# Battery4p.net
KiCad netlist of a schematic drawn in Altium Designer
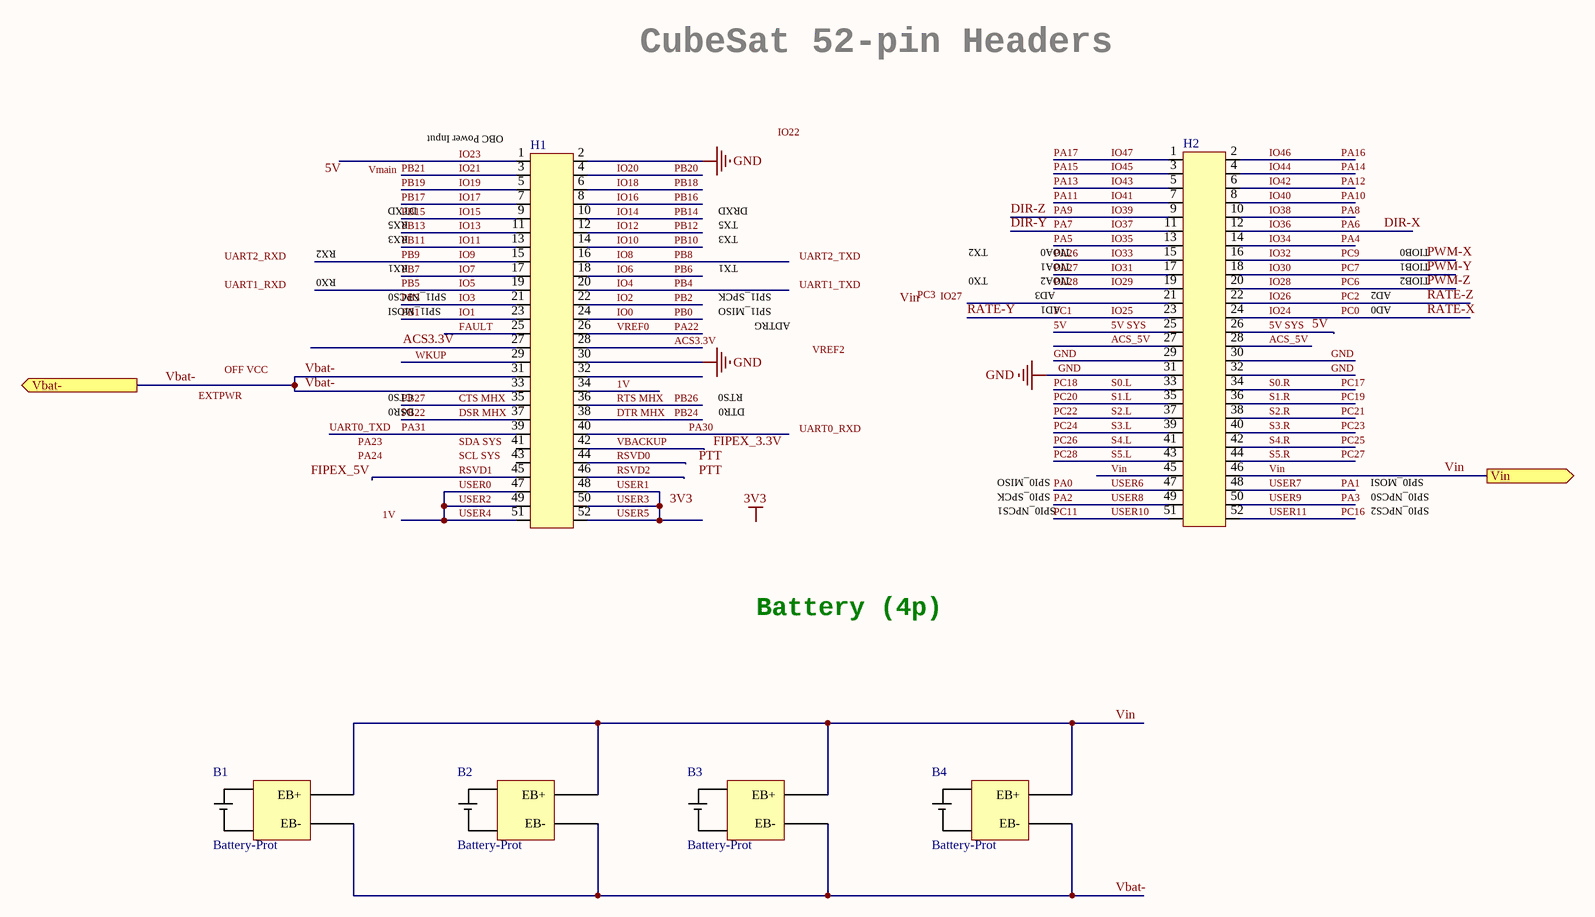
[diagram p0: Battery4p.SchDoc]

(export (version "E")
  (design (tool "Eeschema 10.0.6"))
  (components
    (comp (ref "B1")
      (value "Battery-Prot")
      (footprint "Batt-Prot")
      (libsource (lib "yusend_power") (part "Battery-Prot"))
    )
    (comp (ref "B2")
      (value "Battery-Prot")
      (footprint "Batt-Prot")
      (libsource (lib "yusend_power") (part "Battery-Prot"))
    )
    (comp (ref "B3")
      (value "Battery-Prot")
      (footprint "Batt-Prot")
      (libsource (lib "yusend_power") (part "Battery-Prot"))
    )
    (comp (ref "B4")
      (value "Battery-Prot")
      (footprint "Batt-Prot")
      (libsource (lib "yusend_power") (part "Battery-Prot"))
    )
    (comp (ref "H1")
      (value "H?")
      (footprint "SAMTEC_ESQ_126_39_G_D")
      (description "26X2 header")
      (libsource (lib "SAMTEC_ESQ_126_39_G_D") (part "SAMTEC_ESQ_126_39_G_D"))
    )
    (comp (ref "H2")
      (value "H?")
      (footprint "SAMTEC_ESQ_126_39_G_D")
      (description "26X2 header")
      (libsource (lib "SAMTEC_ESQ_126_39_G_D") (part "SAMTEC_ESQ_126_39_G_D"))
    )
  )
  (nets
    (net (code "1") (name "/1V") (class "Default")
      (node (ref "H1") (pin "34") (pinfunction "34_34") (pintype "passive"))
    )
    (net (code "2") (name "/5V") (class "Default")
      (node (ref "H2") (pin "25") (pinfunction "25_25") (pintype "passive"))
      (node (ref "H2") (pin "26") (pinfunction "26_26") (pintype "passive"))
    )
    (net (code "3") (name "/ACS3.3V") (class "Default")
      (node (ref "H1") (pin "27") (pinfunction "27_27") (pintype "passive"))
      (node (ref "H1") (pin "28") (pinfunction "28_28") (pintype "passive"))
    )
    (net (code "4") (name "/ACS_5V") (class "Default")
      (node (ref "H2") (pin "27") (pinfunction "27_27") (pintype "passive"))
      (node (ref "H2") (pin "28") (pinfunction "28_28") (pintype "passive"))
    )
    (net (code "5") (name "/CTS MHX") (class "Default")
      (node (ref "H1") (pin "35") (pinfunction "35_35") (pintype "passive"))
    )
    (net (code "6") (name "/DIR-X") (class "Default")
      (node (ref "H2") (pin "12") (pinfunction "12_12") (pintype "passive"))
    )
    (net (code "7") (name "/DIR-Y") (class "Default")
      (node (ref "H2") (pin "11") (pinfunction "11_11") (pintype "passive"))
    )
    (net (code "8") (name "/DIR-Z") (class "Default")
      (node (ref "H2") (pin "9") (pinfunction "9_9") (pintype "passive"))
    )
    (net (code "9") (name "/DSR MHX") (class "Default")
      (node (ref "H1") (pin "37") (pinfunction "37_37") (pintype "passive"))
    )
    (net (code "10") (name "/DTR MHX") (class "Default")
      (node (ref "H1") (pin "38") (pinfunction "38_38") (pintype "passive"))
    )
    (net (code "12") (name "/FAULT") (class "Default")
      (node (ref "H1") (pin "25") (pinfunction "25_25") (pintype "passive"))
    )
    (net (code "15") (name "/IO0") (class "Default")
      (node (ref "H1") (pin "24") (pinfunction "24_24") (pintype "passive"))
    )
    (net (code "16") (name "/IO1") (class "Default")
      (node (ref "H1") (pin "23") (pinfunction "23_23") (pintype "passive"))
    )
    (net (code "17") (name "/IO2") (class "Default")
      (node (ref "H1") (pin "22") (pinfunction "22_22") (pintype "passive"))
    )
    (net (code "18") (name "/IO3") (class "Default")
      (node (ref "H1") (pin "21") (pinfunction "21_21") (pintype "passive"))
    )
    (net (code "19") (name "/IO4") (class "Default")
      (node (ref "H1") (pin "20") (pinfunction "20_20") (pintype "passive"))
    )
    (net (code "20") (name "/IO5") (class "Default")
      (node (ref "H1") (pin "19") (pinfunction "19_19") (pintype "passive"))
    )
    (net (code "21") (name "/IO6") (class "Default")
      (node (ref "H1") (pin "18") (pinfunction "18_18") (pintype "passive"))
    )
    (net (code "22") (name "/IO7") (class "Default")
      (node (ref "H1") (pin "17") (pinfunction "17_17") (pintype "passive"))
    )
    (net (code "23") (name "/IO8") (class "Default")
      (node (ref "H1") (pin "16") (pinfunction "16_16") (pintype "passive"))
    )
    (net (code "24") (name "/IO9") (class "Default")
      (node (ref "H1") (pin "15") (pinfunction "15_15") (pintype "passive"))
    )
    (net (code "25") (name "/IO10") (class "Default")
      (node (ref "H1") (pin "14") (pinfunction "14_14") (pintype "passive"))
    )
    (net (code "26") (name "/IO11") (class "Default")
      (node (ref "H1") (pin "13") (pinfunction "13_13") (pintype "passive"))
    )
    (net (code "27") (name "/IO12") (class "Default")
      (node (ref "H1") (pin "12") (pinfunction "12_12") (pintype "passive"))
    )
    (net (code "28") (name "/IO13") (class "Default")
      (node (ref "H1") (pin "11") (pinfunction "11_11") (pintype "passive"))
    )
    (net (code "29") (name "/IO14") (class "Default")
      (node (ref "H1") (pin "10") (pinfunction "10_10") (pintype "passive"))
    )
    (net (code "30") (name "/IO15") (class "Default")
      (node (ref "H1") (pin "9") (pinfunction "9_9") (pintype "passive"))
    )
    (net (code "31") (name "/IO16") (class "Default")
      (node (ref "H1") (pin "8") (pinfunction "8_8") (pintype "passive"))
    )
    (net (code "32") (name "/IO17") (class "Default")
      (node (ref "H1") (pin "7") (pinfunction "7_7") (pintype "passive"))
    )
    (net (code "33") (name "/IO18") (class "Default")
      (node (ref "H1") (pin "6") (pinfunction "6_6") (pintype "passive"))
    )
    (net (code "34") (name "/IO19") (class "Default")
      (node (ref "H1") (pin "5") (pinfunction "5_5") (pintype "passive"))
    )
    (net (code "35") (name "/IO20") (class "Default")
      (node (ref "H1") (pin "4") (pinfunction "4_4") (pintype "passive"))
    )
    (net (code "36") (name "/IO21") (class "Default")
      (node (ref "H1") (pin "3") (pinfunction "3_3") (pintype "passive"))
    )
    (net (code "38") (name "/IO23") (class "Default")
      (node (ref "H1") (pin "1") (pinfunction "1_1") (pintype "passive"))
    )
    (net (code "39") (name "/IO24") (class "Default")
      (node (ref "H2") (pin "24") (pinfunction "24_24") (pintype "passive"))
    )
    (net (code "40") (name "/IO25") (class "Default")
      (node (ref "H2") (pin "23") (pinfunction "23_23") (pintype "passive"))
    )
    (net (code "41") (name "/IO26") (class "Default")
      (node (ref "H2") (pin "22") (pinfunction "22_22") (pintype "passive"))
    )
    (net (code "43") (name "/IO28") (class "Default")
      (node (ref "H2") (pin "20") (pinfunction "20_20") (pintype "passive"))
    )
    (net (code "44") (name "/IO29") (class "Default")
      (node (ref "H2") (pin "19") (pinfunction "19_19") (pintype "passive"))
    )
    (net (code "45") (name "/IO30") (class "Default")
      (node (ref "H2") (pin "18") (pinfunction "18_18") (pintype "passive"))
    )
    (net (code "46") (name "/IO31") (class "Default")
      (node (ref "H2") (pin "17") (pinfunction "17_17") (pintype "passive"))
    )
    (net (code "47") (name "/IO32") (class "Default")
      (node (ref "H2") (pin "16") (pinfunction "16_16") (pintype "passive"))
    )
    (net (code "48") (name "/IO33") (class "Default")
      (node (ref "H2") (pin "15") (pinfunction "15_15") (pintype "passive"))
    )
    (net (code "49") (name "/IO34") (class "Default")
      (node (ref "H2") (pin "14") (pinfunction "14_14") (pintype "passive"))
    )
    (net (code "50") (name "/IO35") (class "Default")
      (node (ref "H2") (pin "13") (pinfunction "13_13") (pintype "passive"))
    )
    (net (code "51") (name "/IO38") (class "Default")
      (node (ref "H2") (pin "10") (pinfunction "10_10") (pintype "passive"))
    )
    (net (code "52") (name "/IO40") (class "Default")
      (node (ref "H2") (pin "8") (pinfunction "8_8") (pintype "passive"))
    )
    (net (code "53") (name "/IO41") (class "Default")
      (node (ref "H2") (pin "7") (pinfunction "7_7") (pintype "passive"))
    )
    (net (code "54") (name "/IO42") (class "Default")
      (node (ref "H2") (pin "6") (pinfunction "6_6") (pintype "passive"))
    )
    (net (code "55") (name "/IO43") (class "Default")
      (node (ref "H2") (pin "5") (pinfunction "5_5") (pintype "passive"))
    )
    (net (code "56") (name "/IO44") (class "Default")
      (node (ref "H2") (pin "4") (pinfunction "4_4") (pintype "passive"))
    )
    (net (code "57") (name "/IO45") (class "Default")
      (node (ref "H2") (pin "3") (pinfunction "3_3") (pintype "passive"))
    )
    (net (code "58") (name "/IO46") (class "Default")
      (node (ref "H2") (pin "2") (pinfunction "2_2") (pintype "passive"))
    )
    (net (code "59") (name "/IO47") (class "Default")
      (node (ref "H2") (pin "1") (pinfunction "1_1") (pintype "passive"))
    )
    (net (code "61") (name "/PA0") (class "Default")
      (node (ref "H2") (pin "47") (pinfunction "47_47") (pintype "passive"))
    )
    (net (code "62") (name "/PA1") (class "Default")
      (node (ref "H2") (pin "48") (pinfunction "48_48") (pintype "passive"))
    )
    (net (code "63") (name "/PA2") (class "Default")
      (node (ref "H2") (pin "49") (pinfunction "49_49") (pintype "passive"))
    )
    (net (code "64") (name "/PA3") (class "Default")
      (node (ref "H2") (pin "50") (pinfunction "50_50") (pintype "passive"))
    )
    (net (code "65") (name "/PA22") (class "Default")
      (node (ref "H1") (pin "26") (pinfunction "26_26") (pintype "passive"))
    )
    (net (code "68") (name "/PA30") (class "Default")
      (node (ref "H1") (pin "40") (pinfunction "40_40") (pintype "passive"))
    )
    (net (code "69") (name "/PA31") (class "Default")
      (node (ref "H1") (pin "39") (pinfunction "39_39") (pintype "passive"))
    )
    (net (code "70") (name "/PB26") (class "Default")
      (node (ref "H1") (pin "36") (pinfunction "36_36") (pintype "passive"))
    )
    (net (code "72") (name "/PC11") (class "Default")
      (node (ref "H2") (pin "51") (pinfunction "51_51") (pintype "passive"))
    )
    (net (code "73") (name "/PC16") (class "Default")
      (node (ref "H2") (pin "52") (pinfunction "52_52") (pintype "passive"))
    )
    (net (code "74") (name "/PC17") (class "Default")
      (node (ref "H2") (pin "34") (pinfunction "34_34") (pintype "passive"))
    )
    (net (code "75") (name "/PC18") (class "Default")
      (node (ref "H2") (pin "33") (pinfunction "33_33") (pintype "passive"))
    )
    (net (code "76") (name "/PC19") (class "Default")
      (node (ref "H2") (pin "36") (pinfunction "36_36") (pintype "passive"))
    )
    (net (code "77") (name "/PC20") (class "Default")
      (node (ref "H2") (pin "35") (pinfunction "35_35") (pintype "passive"))
    )
    (net (code "78") (name "/PC21") (class "Default")
      (node (ref "H2") (pin "38") (pinfunction "38_38") (pintype "passive"))
    )
    (net (code "79") (name "/PC22") (class "Default")
      (node (ref "H2") (pin "37") (pinfunction "37_37") (pintype "passive"))
    )
    (net (code "80") (name "/PC23") (class "Default")
      (node (ref "H2") (pin "40") (pinfunction "40_40") (pintype "passive"))
    )
    (net (code "81") (name "/PC24") (class "Default")
      (node (ref "H2") (pin "39") (pinfunction "39_39") (pintype "passive"))
    )
    (net (code "82") (name "/PC25") (class "Default")
      (node (ref "H2") (pin "42") (pinfunction "42_42") (pintype "passive"))
    )
    (net (code "83") (name "/PC26") (class "Default")
      (node (ref "H2") (pin "41") (pinfunction "41_41") (pintype "passive"))
    )
    (net (code "84") (name "/PC27") (class "Default")
      (node (ref "H2") (pin "44") (pinfunction "44_44") (pintype "passive"))
    )
    (net (code "85") (name "/PC28") (class "Default")
      (node (ref "H2") (pin "43") (pinfunction "43_43") (pintype "passive"))
    )
    (net (code "87") (name "/RSVD0") (class "Default")
      (node (ref "H1") (pin "44") (pinfunction "44_44") (pintype "passive"))
    )
    (net (code "88") (name "/RSVD1") (class "Default")
      (node (ref "H1") (pin "45") (pinfunction "45_45") (pintype "passive"))
    )
    (net (code "89") (name "/RSVD2") (class "Default")
      (node (ref "H1") (pin "46") (pinfunction "46_46") (pintype "passive"))
    )
    (net (code "97") (name "/USER0") (class "Default")
      (node (ref "H1") (pin "47") (pinfunction "47_47") (pintype "passive"))
      (node (ref "H1") (pin "49") (pinfunction "49_49") (pintype "passive"))
      (node (ref "H1") (pin "51") (pinfunction "51_51") (pintype "passive"))
    )
    (net (code "98") (name "/USER1") (class "Default")
      (node (ref "H1") (pin "48") (pinfunction "48_48") (pintype "passive"))
      (node (ref "H1") (pin "50") (pinfunction "50_50") (pintype "passive"))
      (node (ref "H1") (pin "52") (pinfunction "52_52") (pintype "passive"))
    )
    (net (code "99") (name "/VBACKUP") (class "Default")
      (node (ref "H1") (pin "42") (pinfunction "42_42") (pintype "passive"))
    )
    (net (code "101") (name "/Vbat-") (class "Default")
      (node (ref "B1") (pin "EB-") (pinfunction "EB-_EB-") (pintype "passive"))
      (node (ref "B2") (pin "EB-") (pinfunction "EB-_EB-") (pintype "passive"))
      (node (ref "B3") (pin "EB-") (pinfunction "EB-_EB-") (pintype "passive"))
      (node (ref "B4") (pin "EB-") (pinfunction "EB-_EB-") (pintype "passive"))
      (node (ref "H1") (pin "31") (pinfunction "31_31") (pintype "passive"))
      (node (ref "H1") (pin "33") (pinfunction "33_33") (pintype "passive"))
    )
    (net (code "102") (name "/Vin") (class "Default")
      (node (ref "B1") (pin "EB+") (pinfunction "EB+_EB+") (pintype "passive"))
      (node (ref "B2") (pin "EB+") (pinfunction "EB+_EB+") (pintype "passive"))
      (node (ref "B3") (pin "EB+") (pinfunction "EB+_EB+") (pintype "passive"))
      (node (ref "B4") (pin "EB+") (pinfunction "EB+_EB+") (pintype "passive"))
      (node (ref "H2") (pin "45") (pinfunction "45_45") (pintype "passive"))
      (node (ref "H2") (pin "46") (pinfunction "46_46") (pintype "passive"))
    )
    (net (code "104") (name "/WKUP") (class "Default")
      (node (ref "H1") (pin "29") (pinfunction "29_29") (pintype "passive"))
    )
    (net (code "106") (name "GND") (class "Default")
      (node (ref "H1") (pin "2") (pinfunction "2_2") (pintype "passive"))
      (node (ref "H1") (pin "30") (pinfunction "30_30") (pintype "passive"))
      (node (ref "H2") (pin "29") (pinfunction "29_29") (pintype "passive"))
      (node (ref "H2") (pin "30") (pinfunction "30_30") (pintype "passive"))
      (node (ref "H2") (pin "31") (pinfunction "31_31") (pintype "passive"))
      (node (ref "H2") (pin "32") (pinfunction "32_32") (pintype "passive"))
    )
    (net (code "107") (name "unconnected-(H1-Pad32)") (class "Default")
      (node (ref "H1") (pin "32") (pinfunction "32_32") (pintype "passive"))
    )
    (net (code "108") (name "unconnected-(H1-Pad41)") (class "Default")
      (node (ref "H1") (pin "41") (pinfunction "41_41") (pintype "passive"))
    )
    (net (code "109") (name "unconnected-(H1-Pad43)") (class "Default")
      (node (ref "H1") (pin "43") (pinfunction "43_43") (pintype "passive"))
    )
    (net (code "110") (name "unconnected-(H2-Pad21)") (class "Default")
      (node (ref "H2") (pin "21") (pinfunction "21_21") (pintype "passive"))
    )
  )
)
